# OLED_64x32_V2.net
KiCad netlist of a schematic drawn in EAGLE
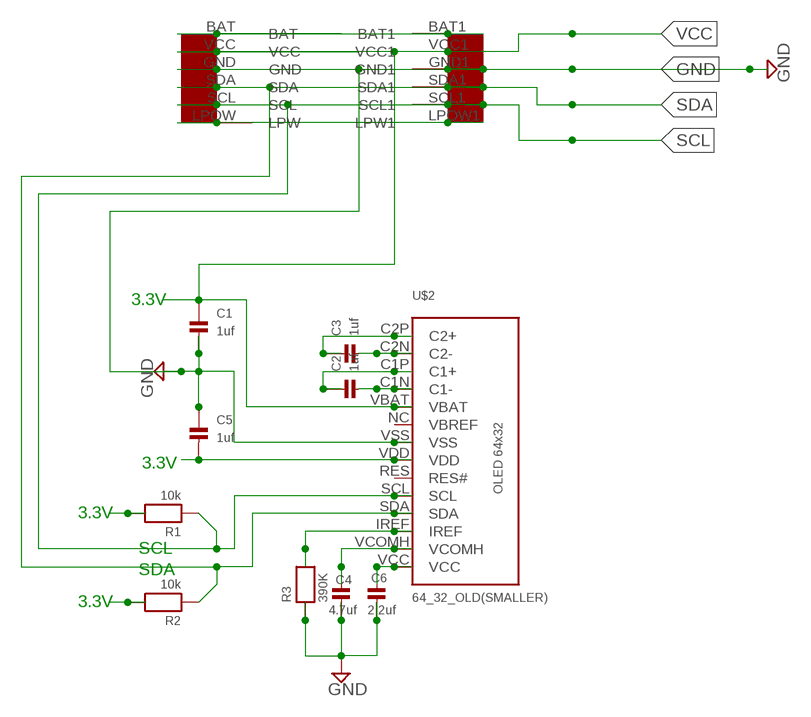
[diagram p0: schematic, sheet 1]

(export (version "E")
  (design (tool "Eeschema 10.0.6"))
  (components
    (comp (ref "C1")
      (value "1uf")
      (footprint "eagle-import:0603")
      (libsource (lib "eagle-import") (part "CAP_CERAMIC0603"))
    )
    (comp (ref "C2")
      (value "1uf")
      (footprint "eagle-import:0603")
      (libsource (lib "eagle-import") (part "CAP_CERAMIC0603"))
    )
    (comp (ref "C3")
      (value "1uf")
      (footprint "eagle-import:0603")
      (libsource (lib "eagle-import") (part "CAP_CERAMIC0603"))
    )
    (comp (ref "C4")
      (value "4.7uf")
      (footprint "eagle-import:0603")
      (libsource (lib "eagle-import") (part "CAP_CERAMIC0603"))
    )
    (comp (ref "C5")
      (value "1uf")
      (footprint "eagle-import:0603")
      (libsource (lib "eagle-import") (part "CAP_CERAMIC0603"))
    )
    (comp (ref "C6")
      (value "2.2uf")
      (footprint "eagle-import:0603")
      (libsource (lib "eagle-import") (part "CAP_CERAMIC0603"))
    )
    (comp (ref "R1")
      (value "10k")
      (footprint "eagle-import:0603")
      (libsource (lib "eagle-import") (part "RESISTOR0603"))
    )
    (comp (ref "R2")
      (value "10k")
      (footprint "eagle-import:0603")
      (libsource (lib "eagle-import") (part "RESISTOR0603"))
    )
    (comp (ref "R3")
      (value "390K")
      (footprint "eagle-import:0603")
      (libsource (lib "eagle-import") (part "RESISTOR0603"))
    )
    (comp (ref "U$1")
      (value "EZ-I2CHEADERV1")
      (footprint "eagle-import:EZ-I2CHEADERV1")
      (libsource (lib "eagle-import") (part "EZ-I2CHEADERV1"))
    )
    (comp (ref "U$2")
      (value "64_32_OLD(SMALLER)")
      (footprint "eagle-import:62_32_OLED(SMALLER)")
      (libsource (lib "eagle-import") (part "64_32_OLD(SMALLER)"))
    )
  )
  (nets
    (net (code "1") (name "GND") (class "Default")
      (node (ref "C1") (pin "2") (pinfunction "P$2_2") (pintype "passive"))
      (node (ref "C4") (pin "2") (pinfunction "P$2_2") (pintype "passive"))
      (node (ref "C5") (pin "1") (pinfunction "P$1_1") (pintype "passive"))
      (node (ref "C6") (pin "2") (pinfunction "P$2_2") (pintype "passive"))
      (node (ref "R3") (pin "1") (pinfunction "1_1") (pintype "passive"))
      (node (ref "U$1") (pin "GND") (pinfunction "GND_GND") (pintype "bidirectional"))
      (node (ref "U$1") (pin "GND1") (pinfunction "GND1_GND1") (pintype "bidirectional"))
      (node (ref "U$2") (pin "VSS") (pinfunction "VSS_VSS") (pintype "bidirectional"))
    )
    (net (code "2") (name "Net-(C2-P$1)") (class "Default")
      (node (ref "C2") (pin "1") (pinfunction "P$1_1") (pintype "passive"))
      (node (ref "U$2") (pin "C1P") (pinfunction "C1+_C1P") (pintype "bidirectional"))
    )
    (net (code "3") (name "Net-(C2-P$2)") (class "Default")
      (node (ref "C2") (pin "2") (pinfunction "P$2_2") (pintype "passive"))
      (node (ref "U$2") (pin "C1N") (pinfunction "C1-_C1N") (pintype "bidirectional"))
    )
    (net (code "4") (name "Net-(C3-P$1)") (class "Default")
      (node (ref "C3") (pin "1") (pinfunction "P$1_1") (pintype "passive"))
      (node (ref "U$2") (pin "C2P") (pinfunction "C2+_C2P") (pintype "bidirectional"))
    )
    (net (code "5") (name "Net-(C3-P$2)") (class "Default")
      (node (ref "C3") (pin "2") (pinfunction "P$2_2") (pintype "passive"))
      (node (ref "U$2") (pin "C2N") (pinfunction "C2-_C2N") (pintype "bidirectional"))
    )
    (net (code "6") (name "Net-(C4-P$1)") (class "Default")
      (node (ref "C4") (pin "1") (pinfunction "P$1_1") (pintype "passive"))
      (node (ref "U$2") (pin "VCOMH") (pinfunction "VCOMH_VCOMH") (pintype "bidirectional"))
    )
    (net (code "7") (name "Net-(C6-P$1)") (class "Default")
      (node (ref "C6") (pin "1") (pinfunction "P$1_1") (pintype "passive"))
      (node (ref "U$2") (pin "VCC") (pinfunction "VCC_VCC") (pintype "bidirectional"))
    )
    (net (code "8") (name "Net-(R3-Pad2)") (class "Default")
      (node (ref "R3") (pin "2") (pinfunction "2_2") (pintype "passive"))
      (node (ref "U$2") (pin "IREF") (pinfunction "IREF_IREF") (pintype "bidirectional"))
    )
    (net (code "9") (name "Net-(U$1-LPW)") (class "Default")
      (node (ref "U$1") (pin "LPOW") (pinfunction "LPW_LPOW") (pintype "bidirectional"))
      (node (ref "U$1") (pin "LPOW1") (pinfunction "LPW1_LPOW1") (pintype "bidirectional"))
    )
    (net (code "10") (name "Net-(U$1-PadBAT)") (class "Default")
      (node (ref "U$1") (pin "BAT") (pinfunction "BAT_BAT") (pintype "bidirectional"))
      (node (ref "U$1") (pin "BAT1") (pinfunction "BAT1_BAT1") (pintype "bidirectional"))
    )
    (net (code "11") (name "SCL") (class "Default")
      (node (ref "R1") (pin "1") (pinfunction "1_1") (pintype "passive"))
      (node (ref "U$1") (pin "SCL") (pinfunction "SCL_SCL") (pintype "bidirectional"))
      (node (ref "U$1") (pin "SCL1") (pinfunction "SCL1_SCL1") (pintype "bidirectional"))
      (node (ref "U$2") (pin "SCL") (pinfunction "SCL_SCL") (pintype "bidirectional"))
    )
    (net (code "12") (name "SDA") (class "Default")
      (node (ref "R2") (pin "1") (pinfunction "1_1") (pintype "passive"))
      (node (ref "U$1") (pin "SDA") (pinfunction "SDA_SDA") (pintype "bidirectional"))
      (node (ref "U$1") (pin "SDA1") (pinfunction "SDA1_SDA1") (pintype "bidirectional"))
      (node (ref "U$2") (pin "SDA") (pinfunction "SDA_SDA") (pintype "bidirectional"))
    )
    (net (code "13") (name "VCC") (class "Default")
      (node (ref "C1") (pin "1") (pinfunction "P$1_1") (pintype "passive"))
      (node (ref "C5") (pin "2") (pinfunction "P$2_2") (pintype "passive"))
      (node (ref "R1") (pin "2") (pinfunction "2_2") (pintype "passive"))
      (node (ref "R2") (pin "2") (pinfunction "2_2") (pintype "passive"))
      (node (ref "U$1") (pin "VCC") (pinfunction "VCC_VCC") (pintype "bidirectional"))
      (node (ref "U$1") (pin "VCC1") (pinfunction "VCC1_VCC1") (pintype "bidirectional"))
      (node (ref "U$2") (pin "VBAT") (pinfunction "VBAT_VBAT") (pintype "bidirectional"))
      (node (ref "U$2") (pin "VDD") (pinfunction "VDD_VDD") (pintype "bidirectional"))
    )
    (net (code "14") (name "unconnected-(U$2-RES#-PadRES)") (class "Default")
      (node (ref "U$2") (pin "RES") (pinfunction "RES#_RES") (pintype "bidirectional"))
    )
    (net (code "15") (name "unconnected-(U$2-VBREF-PadNC)") (class "Default")
      (node (ref "U$2") (pin "NC") (pinfunction "VBREF_NC") (pintype "bidirectional"))
    )
  )
)
